# 1_-_MCU.net
KiCad netlist of a schematic drawn in Altium Designer
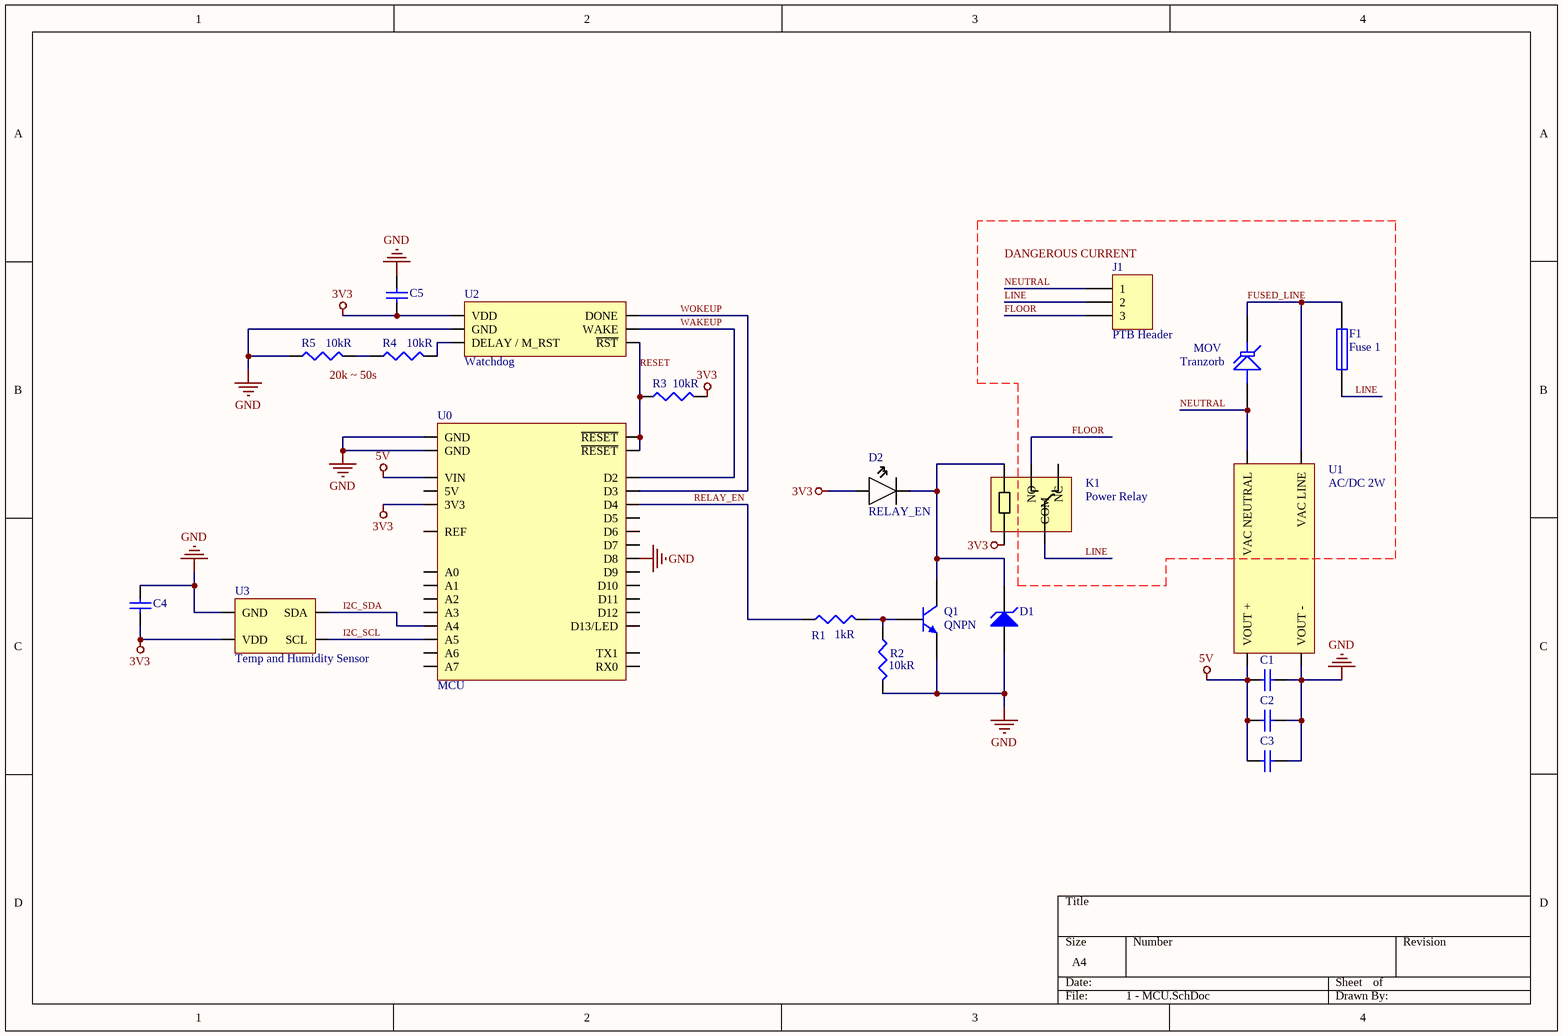
[diagram p0: 1 - MCU.SchDoc]

(export (version "E")
  (design (tool "Eeschema 10.0.6"))
  (components
    (comp (ref "C1")
      (value "4.7uF")
      (footprint "SMD_1206_C_SMALL")
      (description "Capacitor (Semiconductor SIM Model)")
      (fields
        (field (name "MANUFACTURER") "Murata")
        (field (name "MANUFACTURER PART NUMBER") "GCM31CC71H475MA03K")
      )
      (libsource (lib "Miscellaneous Devices") (part "Cap Semi"))
    )
    (comp (ref "C2")
      (value "4.7uF")
      (footprint "SMD_1206_C_SMALL")
      (description "Capacitor (Semiconductor SIM Model)")
      (fields
        (field (name "MANUFACTURER") "Murata")
        (field (name "MANUFACTURER PART NUMBER") "GCM31CC71H475MA03K")
      )
      (libsource (lib "Miscellaneous Devices") (part "Cap Semi"))
    )
    (comp (ref "C3")
      (value "Cap Semi")
      (footprint "SMD_0805_C")
      (fields
        (field (name "MANUFACTURER") "Kyocera AVX")
        (field (name "MANUFACTURER PART NUMBER") "08055C104K4Z2A")
        (field (name "TOLERANCE") "10%")
      )
      (libsource (lib "Miscellaneous Devices") (part "Cap Semi"))
    )
    (comp (ref "C4")
      (value "Cap Semi")
      (footprint "SMD_0805_C")
      (fields
        (field (name "MANUFACTURER") "Kyocera AVX")
        (field (name "MANUFACTURER PART NUMBER") "08055C104K4Z2A")
        (field (name "TOLERANCE") "10%")
      )
      (libsource (lib "Miscellaneous Devices") (part "Cap Semi"))
    )
    (comp (ref "C5")
      (value "Cap Semi")
      (footprint "SMD_0805_C")
      (fields
        (field (name "MANUFACTURER") "Kyocera AVX")
        (field (name "MANUFACTURER PART NUMBER") "08055C104K4Z2A")
        (field (name "TOLERANCE") "10%")
      )
      (libsource (lib "Miscellaneous Devices") (part "Cap Semi"))
    )
    (comp (ref "D1")
      (value "D Zener")
      (footprint "SOD323 / SC-76")
      (description "TVS DIODE 3.3VWM 13VC")
      (fields
        (field (name "MANUFACTURER") "Nexperia")
        (field (name "MANUFACTURER PART NUMBER") "BZX384-B3V3,115")
      )
      (libsource (lib "Miscellaneous Devices") (part "D Zener"))
    )
    (comp (ref "D2")
      (value "RELAY_EN")
      (footprint "LED0603")
      (fields
        (field (name "MANUFACTURER") "Stanley Electric")
        (field (name "MANUFACTURER PART NUMBER") "SJW1151CKS-100-TR")
      )
      (libsource (lib "Parts") (part "LED"))
    )
    (comp (ref "F1")
      (value "Fuse 1")
      (footprint "Bourns SF-3812TL")
      (description "Fuse")
      (fields
        (field (name "MANUFACTURER") "Bourns")
        (field (name "MANUFACTURER PART NUMBER") "SF-3812TL050T-2")
      )
      (libsource (lib "Miscellaneous Devices") (part "Fuse 1"))
    )
    (comp (ref "J1")
      (value "PTB Header")
      (footprint "TBL005A-500-03GY")
      (description "Header, 3-Pin")
      (fields
        (field (name "MANUFACTURER") "CUI Devices")
        (field (name "MANUFACTURER PART NUMBER") "TBL005A-500-03GY-2WT")
        (field (name "PUBLISHER") "Altium Limited")
      )
      (libsource (lib "Miscellaneous Connectors") (part "Header 3"))
    )
    (comp (ref "K1")
      (value "Power Relay")
      (footprint "G5LE-14")
      (fields (field (name "MANUFACTURER") "Omron") (field (name "MANUFACTURER PART NUMBER") "G5LE-14-DC3"))
      (libsource (lib "BLEFloor") (part "Relay, SPDT"))
    )
    (comp (ref "MOV")
      (value "Tranzorb")
      (footprint "MOV_14mm_7.5")
      (description "Transient Voltage Suppression (TVS) Diode")
      (fields (field (name "MANUFACTURER") "Bourns") (field (name "MANUFACTURER PART NUMBER") "MOV-14D391K"))
      (libsource (lib "Miscellaneous Devices") (part "Tranzorb"))
    )
    (comp (ref "Q1")
      (value "QNPN")
      (footprint "SOT-23B_N")
      (description "TRANS NPN MED PWR 400V SOT23F-3")
      (fields (field (name "MANUFACTURER") "Diodes") (field (name "MANUFACTURER PART NUMBER") "BC847A-7-F"))
      (libsource (lib "Miscellaneous Devices") (part "QNPN"))
    )
    (comp (ref "R1")
      (value "Res3")
      (footprint "SMD_0603_R")
      (description "RES 1K OHM 1/10W 1% 0603 SMD")
      (fields
        (field (name "MANUFACTURER") "Panasonic")
        (field (name "MANUFACTURER PART NUMBER") "ERJ3EKF1001V")
        (field (name "RESISTANCE") "1kR")
      )
      (libsource (lib "Miscellaneous Devices") (part "Res3"))
    )
    (comp (ref "R2")
      (value "Res3")
      (footprint "SMD_0603_R")
      (description "RES 10K OHM 1/10W 1% 0603 SMD")
      (fields
        (field (name "MANUFACTURER") "Panasonic")
        (field (name "MANUFACTURER PART NUMBER") "ERJ-3EKF1002V")
        (field (name "RESISTANCE") "10kR")
      )
      (libsource (lib "Miscellaneous Devices") (part "Res3"))
    )
    (comp (ref "R3")
      (value "Res3")
      (footprint "SMD_0603_R")
      (description "RES 10K OHM 1/10W 1% 0603 SMD")
      (fields
        (field (name "MANUFACTURER") "Panasonic")
        (field (name "MANUFACTURER PART NUMBER") "ERJ-3EKF1002V")
        (field (name "RESISTANCE") "10kR")
      )
      (libsource (lib "Miscellaneous Devices") (part "Res3"))
    )
    (comp (ref "R4")
      (value "Res3")
      (footprint "SMD_0603_R")
      (description "RES 10K OHM 1/10W 1% 0603 SMD")
      (fields
        (field (name "MANUFACTURER") "Panasonic")
        (field (name "MANUFACTURER PART NUMBER") "ERJ-3EKF1002V")
        (field (name "RESISTANCE") "10kR")
      )
      (libsource (lib "Miscellaneous Devices") (part "Res3"))
    )
    (comp (ref "R5")
      (value "Res3")
      (footprint "SMD_0603_R")
      (description "RES 10K OHM 1/10W 1% 0603 SMD")
      (fields
        (field (name "MANUFACTURER") "Panasonic")
        (field (name "MANUFACTURER PART NUMBER") "ERJ-3EKF1002V")
        (field (name "RESISTANCE") "10kR")
      )
      (libsource (lib "Miscellaneous Devices") (part "Res3"))
    )
    (comp (ref "U0")
      (value "MCU")
      (footprint "BLENano33IoT")
      (libsource (lib "BLEFloor") (part "ArduinoNano33IoT"))
    )
    (comp (ref "U1")
      (value "AC/DC 2W")
      (footprint "RAC02-GA")
      (fields (field (name "MANUFACTURER") "Recom") (field (name "MANUFACTURER PART NUMBER") "RAC02-05SGA"))
      (libsource (lib "BLEFloor") (part "ADDC Wandler"))
    )
    (comp (ref "U2")
      (value "Watchdog")
      (footprint "SOT23-6_L")
      (fields
        (field (name "MANUFACTURER") "Texas Instruments")
        (field (name "MANUFACTURER PART NUMBER") "TPL5010DDCR")
      )
      (libsource (lib "BLEFloor") (part "TPL5010"))
    )
    (comp (ref "U3")
      (value "Temp and Humidity Sensor")
      (footprint "3x3 6pin DFN")
      (fields
        (field (name "MANUFACTURER") "Silicon Labs")
        (field (name "MANUFACTURER PART NUMBER") "SI7020-A20-GM")
      )
      (libsource (lib "BLEFloor") (part "Si7020"))
    )
  )
  (nets
    (net (code "1") (name "/FLOOR") (class "Default")
      (node (ref "J1") (pin "3") (pinfunction "3_3") (pintype "passive"))
      (node (ref "K1") (pin "3") (pinfunction "NO_3") (pintype "power_in"))
    )
    (net (code "2") (name "/FUSED_LINE") (class "Default")
      (node (ref "F1") (pin "2") (pinfunction "2_2") (pintype "passive"))
      (node (ref "MOV") (pin "2") (pinfunction "K_2") (pintype "passive"))
      (node (ref "U1") (pin "1") (pinfunction "VAC_LINE_1") (pintype "power_in"))
    )
    (net (code "3") (name "/I2C_SCL") (class "Default")
      (node (ref "U0") (pin "9") (pinfunction "A5_9") (pintype "power_in"))
      (node (ref "U3") (pin "6") (pinfunction "SCL_6") (pintype "power_in"))
    )
    (net (code "4") (name "/I2C_SDA") (class "Default")
      (node (ref "U0") (pin "8") (pinfunction "A4_8") (pintype "power_in"))
      (node (ref "U3") (pin "1") (pinfunction "SDA_1") (pintype "power_in"))
    )
    (net (code "5") (name "/LINE") (class "Default")
      (node (ref "F1") (pin "1") (pinfunction "1_1") (pintype "passive"))
      (node (ref "J1") (pin "2") (pinfunction "2_2") (pintype "passive"))
      (node (ref "K1") (pin "1") (pinfunction "COM_1") (pintype "power_in"))
    )
    (net (code "6") (name "/NEUTRAL") (class "Default")
      (node (ref "J1") (pin "1") (pinfunction "1_1") (pintype "passive"))
      (node (ref "MOV") (pin "1") (pinfunction "A_1") (pintype "passive"))
      (node (ref "U1") (pin "2") (pinfunction "VAC_NEUTRAL_2") (pintype "power_in"))
    )
    (net (code "7") (name "/RELAY_EN") (class "Default")
      (node (ref "R1") (pin "1") (pinfunction "1_1") (pintype "passive"))
      (node (ref "U0") (pin "22") (pinfunction "D4_22") (pintype "power_in"))
    )
    (net (code "8") (name "/RESET") (class "Default")
      (node (ref "R3") (pin "1") (pinfunction "1_1") (pintype "passive"))
      (node (ref "U0") (pin "13") (pinfunction "~{RESET}_13") (pintype "power_in"))
      (node (ref "U0") (pin "18") (pinfunction "~{RESET}_18") (pintype "power_in"))
      (node (ref "U2") (pin "6") (pinfunction "~{RST}_6") (pintype "power_in"))
    )
    (net (code "9") (name "/WAKEUP") (class "Default")
      (node (ref "U0") (pin "20") (pinfunction "D2_20") (pintype "power_in"))
      (node (ref "U2") (pin "5") (pinfunction "WAKE_5") (pintype "power_in"))
    )
    (net (code "10") (name "/WOKEUP") (class "Default")
      (node (ref "U0") (pin "21") (pinfunction "D3_21") (pintype "power_in"))
      (node (ref "U2") (pin "4") (pinfunction "DONE_4") (pintype "power_in"))
    )
    (net (code "11") (name "3V3") (class "Default")
      (node (ref "C4") (pin "2") (pinfunction "2_2") (pintype "passive"))
      (node (ref "C5") (pin "2") (pinfunction "2_2") (pintype "passive"))
      (node (ref "D2") (pin "A") (pinfunction "ANODE_A") (pintype "passive"))
      (node (ref "K1") (pin "5") (pinfunction "COILB_5") (pintype "power_in"))
      (node (ref "R3") (pin "2") (pinfunction "2_2") (pintype "passive"))
      (node (ref "U0") (pin "2") (pinfunction "3V3_2") (pintype "power_in"))
      (node (ref "U2") (pin "1") (pinfunction "VDD_1") (pintype "power_in"))
      (node (ref "U3") (pin "5") (pinfunction "VDD_5") (pintype "power_in"))
    )
    (net (code "12") (name "5V") (class "Default")
      (node (ref "C1") (pin "2") (pinfunction "2_2") (pintype "passive"))
      (node (ref "C2") (pin "2") (pinfunction "2_2") (pintype "passive"))
      (node (ref "C3") (pin "2") (pinfunction "2_2") (pintype "passive"))
      (node (ref "U0") (pin "15") (pinfunction "VIN_15") (pintype "power_in"))
      (node (ref "U1") (pin "4") (pinfunction "VOUT_+_4") (pintype "power_in"))
    )
    (net (code "13") (name "GND") (class "Default")
      (node (ref "C1") (pin "1") (pinfunction "1_1") (pintype "passive"))
      (node (ref "C2") (pin "1") (pinfunction "1_1") (pintype "passive"))
      (node (ref "C3") (pin "1") (pinfunction "1_1") (pintype "passive"))
      (node (ref "C4") (pin "1") (pinfunction "1_1") (pintype "passive"))
      (node (ref "C5") (pin "1") (pinfunction "1_1") (pintype "passive"))
      (node (ref "D1") (pin "1") (pinfunction "A_1") (pintype "passive"))
      (node (ref "Q1") (pin "3") (pinfunction "E_3") (pintype "passive"))
      (node (ref "R2") (pin "2") (pinfunction "2_2") (pintype "passive"))
      (node (ref "R5") (pin "1") (pinfunction "1_1") (pintype "passive"))
      (node (ref "U0") (pin "14") (pinfunction "GND_14") (pintype "power_in"))
      (node (ref "U0") (pin "19") (pinfunction "GND_19") (pintype "power_in"))
      (node (ref "U0") (pin "26") (pinfunction "D8_26") (pintype "power_in"))
      (node (ref "U1") (pin "3") (pinfunction "VOUT_-_3") (pintype "power_in"))
      (node (ref "U2") (pin "2") (pinfunction "GND_2") (pintype "power_in"))
      (node (ref "U3") (pin "2") (pinfunction "GND_2") (pintype "power_in"))
    )
    (net (code "14") (name "Net-(D1-K)") (class "Default")
      (node (ref "D1") (pin "2") (pinfunction "K_2") (pintype "passive"))
      (node (ref "D2") (pin "C") (pinfunction "CATHODE_C") (pintype "passive"))
      (node (ref "K1") (pin "2") (pinfunction "COILA_2") (pintype "power_in"))
      (node (ref "Q1") (pin "1") (pinfunction "C_1") (pintype "passive"))
    )
    (net (code "15") (name "Net-(Q1-B)") (class "Default")
      (node (ref "Q1") (pin "2") (pinfunction "B_2") (pintype "passive"))
      (node (ref "R1") (pin "2") (pinfunction "2_2") (pintype "passive"))
      (node (ref "R2") (pin "1") (pinfunction "1_1") (pintype "passive"))
    )
    (net (code "16") (name "Net-(R4-Pad1)") (class "Default")
      (node (ref "R4") (pin "1") (pinfunction "1_1") (pintype "passive"))
      (node (ref "R5") (pin "2") (pinfunction "2_2") (pintype "passive"))
    )
    (net (code "17") (name "Net-(U2-DELAY_{slash}_M_RST)") (class "Default")
      (node (ref "R4") (pin "2") (pinfunction "2_2") (pintype "passive"))
      (node (ref "U2") (pin "3") (pinfunction "DELAY_/_M_RST_3") (pintype "power_in"))
    )
    (net (code "18") (name "unconnected-(K1-NC-Pad4)") (class "Default")
      (node (ref "K1") (pin "4") (pinfunction "NC_4") (pintype "power_in"))
    )
    (net (code "19") (name "unconnected-(U0-5V-Pad12)") (class "Default")
      (node (ref "U0") (pin "12") (pinfunction "5V_12") (pintype "power_in"))
    )
    (net (code "20") (name "unconnected-(U0-A0-Pad4)") (class "Default")
      (node (ref "U0") (pin "4") (pinfunction "A0_4") (pintype "power_in"))
    )
    (net (code "21") (name "unconnected-(U0-A1-Pad5)") (class "Default")
      (node (ref "U0") (pin "5") (pinfunction "A1_5") (pintype "power_in"))
    )
    (net (code "22") (name "unconnected-(U0-A2-Pad6)") (class "Default")
      (node (ref "U0") (pin "6") (pinfunction "A2_6") (pintype "power_in"))
    )
    (net (code "23") (name "unconnected-(U0-A3-Pad7)") (class "Default")
      (node (ref "U0") (pin "7") (pinfunction "A3_7") (pintype "power_in"))
    )
    (net (code "24") (name "unconnected-(U0-A6-Pad10)") (class "Default")
      (node (ref "U0") (pin "10") (pinfunction "A6_10") (pintype "power_in"))
    )
    (net (code "25") (name "unconnected-(U0-A7-Pad11)") (class "Default")
      (node (ref "U0") (pin "11") (pinfunction "A7_11") (pintype "power_in"))
    )
    (net (code "26") (name "unconnected-(U0-D5-Pad23)") (class "Default")
      (node (ref "U0") (pin "23") (pinfunction "D5_23") (pintype "power_in"))
    )
    (net (code "27") (name "unconnected-(U0-D6-Pad24)") (class "Default")
      (node (ref "U0") (pin "24") (pinfunction "D6_24") (pintype "power_in"))
    )
    (net (code "28") (name "unconnected-(U0-D7-Pad25)") (class "Default")
      (node (ref "U0") (pin "25") (pinfunction "D7_25") (pintype "power_in"))
    )
    (net (code "29") (name "unconnected-(U0-D9-Pad27)") (class "Default")
      (node (ref "U0") (pin "27") (pinfunction "D9_27") (pintype "power_in"))
    )
    (net (code "30") (name "unconnected-(U0-D10-Pad28)") (class "Default")
      (node (ref "U0") (pin "28") (pinfunction "D10_28") (pintype "power_in"))
    )
    (net (code "31") (name "unconnected-(U0-D11-Pad29)") (class "Default")
      (node (ref "U0") (pin "29") (pinfunction "D11_29") (pintype "power_in"))
    )
    (net (code "32") (name "unconnected-(U0-D12-Pad30)") (class "Default")
      (node (ref "U0") (pin "30") (pinfunction "D12_30") (pintype "power_in"))
    )
    (net (code "33") (name "unconnected-(U0-D13{slash}LED-Pad1)") (class "Default")
      (node (ref "U0") (pin "1") (pinfunction "D13/LED_1") (pintype "power_in"))
    )
    (net (code "34") (name "unconnected-(U0-REF-Pad3)") (class "Default")
      (node (ref "U0") (pin "3") (pinfunction "REF_3") (pintype "power_in"))
    )
    (net (code "35") (name "unconnected-(U0-RX0-Pad17)") (class "Default")
      (node (ref "U0") (pin "17") (pinfunction "RX0_17") (pintype "power_in"))
    )
    (net (code "36") (name "unconnected-(U0-TX1-Pad16)") (class "Default")
      (node (ref "U0") (pin "16") (pinfunction "TX1_16") (pintype "power_in"))
    )
  )
)
